# bullbridge_test.net
KiCad netlist of a schematic drawn in EAGLE
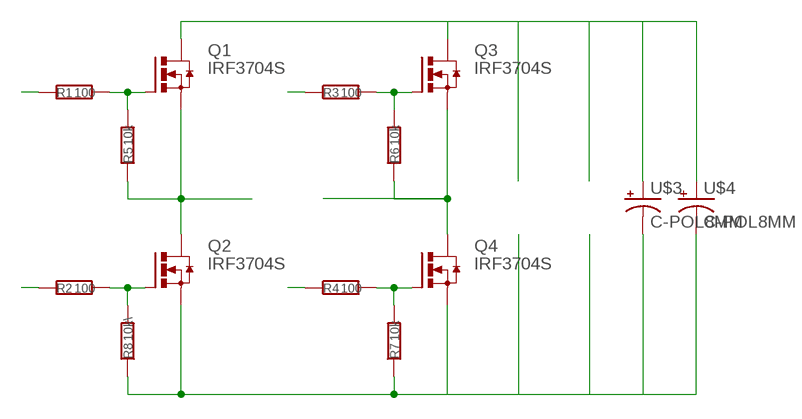
[diagram p0: schematic, sheet 1]

(export (version "E")
  (design (tool "Eeschema 10.0.6"))
  (components
    (comp (ref "Q1")
      (value "IRF3704S")
      (footprint "eagle-import:D2PACK")
      (libsource (lib "eagle-import") (part "IRF3704S"))
    )
    (comp (ref "Q2")
      (value "IRF3704S")
      (footprint "eagle-import:D2PACK")
      (libsource (lib "eagle-import") (part "IRF3704S"))
    )
    (comp (ref "Q3")
      (value "IRF3704S")
      (footprint "eagle-import:D2PACK")
      (libsource (lib "eagle-import") (part "IRF3704S"))
    )
    (comp (ref "Q4")
      (value "IRF3704S")
      (footprint "eagle-import:D2PACK")
      (libsource (lib "eagle-import") (part "IRF3704S"))
    )
    (comp (ref "R1")
      (value "100")
      (footprint "eagle-import:R0805")
      (libsource (lib "eagle-import") (part "R0805"))
    )
    (comp (ref "R2")
      (value "100")
      (footprint "eagle-import:R0805")
      (libsource (lib "eagle-import") (part "R0805"))
    )
    (comp (ref "R3")
      (value "100")
      (footprint "eagle-import:R0805")
      (libsource (lib "eagle-import") (part "R0805"))
    )
    (comp (ref "R4")
      (value "100")
      (footprint "eagle-import:R0805")
      (libsource (lib "eagle-import") (part "R0805"))
    )
    (comp (ref "R5")
      (value "10k")
      (footprint "eagle-import:R0805")
      (libsource (lib "eagle-import") (part "R0805"))
    )
    (comp (ref "R6")
      (value "10k")
      (footprint "eagle-import:R0805")
      (libsource (lib "eagle-import") (part "R0805"))
    )
    (comp (ref "R7")
      (value "10k")
      (footprint "eagle-import:R0805")
      (libsource (lib "eagle-import") (part "R0805"))
    )
    (comp (ref "R8")
      (value "10k\\")
      (footprint "eagle-import:R0805")
      (libsource (lib "eagle-import") (part "R0805"))
    )
    (comp (ref "U$3")
      (value "C-POL8MM")
      (footprint "eagle-import:PCAP8")
      (libsource (lib "eagle-import") (part "C-POL8MM"))
    )
    (comp (ref "U$4")
      (value "C-POL8MM")
      (footprint "eagle-import:PCAP8")
      (libsource (lib "eagle-import") (part "C-POL8MM"))
    )
  )
  (nets
    (net (code "1") (name "Net-(Q1-D)") (class "Default")
      (node (ref "Q1") (pin "2") (pinfunction "D_2") (pintype "passive"))
      (node (ref "Q3") (pin "2") (pinfunction "D_2") (pintype "passive"))
      (node (ref "U$3") (pin "P$1") (pinfunction "+_P$1") (pintype "passive"))
      (node (ref "U$4") (pin "P$1") (pinfunction "+_P$1") (pintype "passive"))
    )
    (net (code "2") (name "Net-(Q1-G)") (class "Default")
      (node (ref "Q1") (pin "1") (pinfunction "G_1") (pintype "passive"))
      (node (ref "R1") (pin "2") (pinfunction "2_2") (pintype "passive"))
      (node (ref "R5") (pin "2") (pinfunction "2_2") (pintype "passive"))
    )
    (net (code "3") (name "Net-(Q1-S)") (class "Default")
      (node (ref "Q1") (pin "3") (pinfunction "S_3") (pintype "passive"))
      (node (ref "Q2") (pin "2") (pinfunction "D_2") (pintype "passive"))
      (node (ref "R5") (pin "1") (pinfunction "1_1") (pintype "passive"))
    )
    (net (code "4") (name "Net-(Q2-G)") (class "Default")
      (node (ref "Q2") (pin "1") (pinfunction "G_1") (pintype "passive"))
      (node (ref "R2") (pin "2") (pinfunction "2_2") (pintype "passive"))
      (node (ref "R8") (pin "2") (pinfunction "2_2") (pintype "passive"))
    )
    (net (code "5") (name "Net-(Q2-S)") (class "Default")
      (node (ref "Q2") (pin "3") (pinfunction "S_3") (pintype "passive"))
      (node (ref "Q4") (pin "3") (pinfunction "S_3") (pintype "passive"))
      (node (ref "R7") (pin "1") (pinfunction "1_1") (pintype "passive"))
      (node (ref "R8") (pin "1") (pinfunction "1_1") (pintype "passive"))
      (node (ref "U$3") (pin "P$2") (pinfunction "-_P$2") (pintype "passive"))
      (node (ref "U$4") (pin "P$2") (pinfunction "-_P$2") (pintype "passive"))
    )
    (net (code "6") (name "Net-(Q3-G)") (class "Default")
      (node (ref "Q3") (pin "1") (pinfunction "G_1") (pintype "passive"))
      (node (ref "R3") (pin "2") (pinfunction "2_2") (pintype "passive"))
      (node (ref "R6") (pin "2") (pinfunction "2_2") (pintype "passive"))
    )
    (net (code "7") (name "Net-(Q3-S)") (class "Default")
      (node (ref "Q3") (pin "3") (pinfunction "S_3") (pintype "passive"))
      (node (ref "Q4") (pin "2") (pinfunction "D_2") (pintype "passive"))
      (node (ref "R6") (pin "1") (pinfunction "1_1") (pintype "passive"))
    )
    (net (code "8") (name "Net-(Q4-G)") (class "Default")
      (node (ref "Q4") (pin "1") (pinfunction "G_1") (pintype "passive"))
      (node (ref "R4") (pin "2") (pinfunction "2_2") (pintype "passive"))
      (node (ref "R7") (pin "2") (pinfunction "2_2") (pintype "passive"))
    )
    (net (code "9") (name "unconnected-(R1-Pad1)") (class "Default")
      (node (ref "R1") (pin "1") (pinfunction "1_1") (pintype "passive"))
    )
    (net (code "10") (name "unconnected-(R2-Pad1)") (class "Default")
      (node (ref "R2") (pin "1") (pinfunction "1_1") (pintype "passive"))
    )
    (net (code "11") (name "unconnected-(R3-Pad1)") (class "Default")
      (node (ref "R3") (pin "1") (pinfunction "1_1") (pintype "passive"))
    )
    (net (code "12") (name "unconnected-(R4-Pad1)") (class "Default")
      (node (ref "R4") (pin "1") (pinfunction "1_1") (pintype "passive"))
    )
  )
)
